# Connectors.net
KiCad netlist of a schematic drawn in Altium Designer
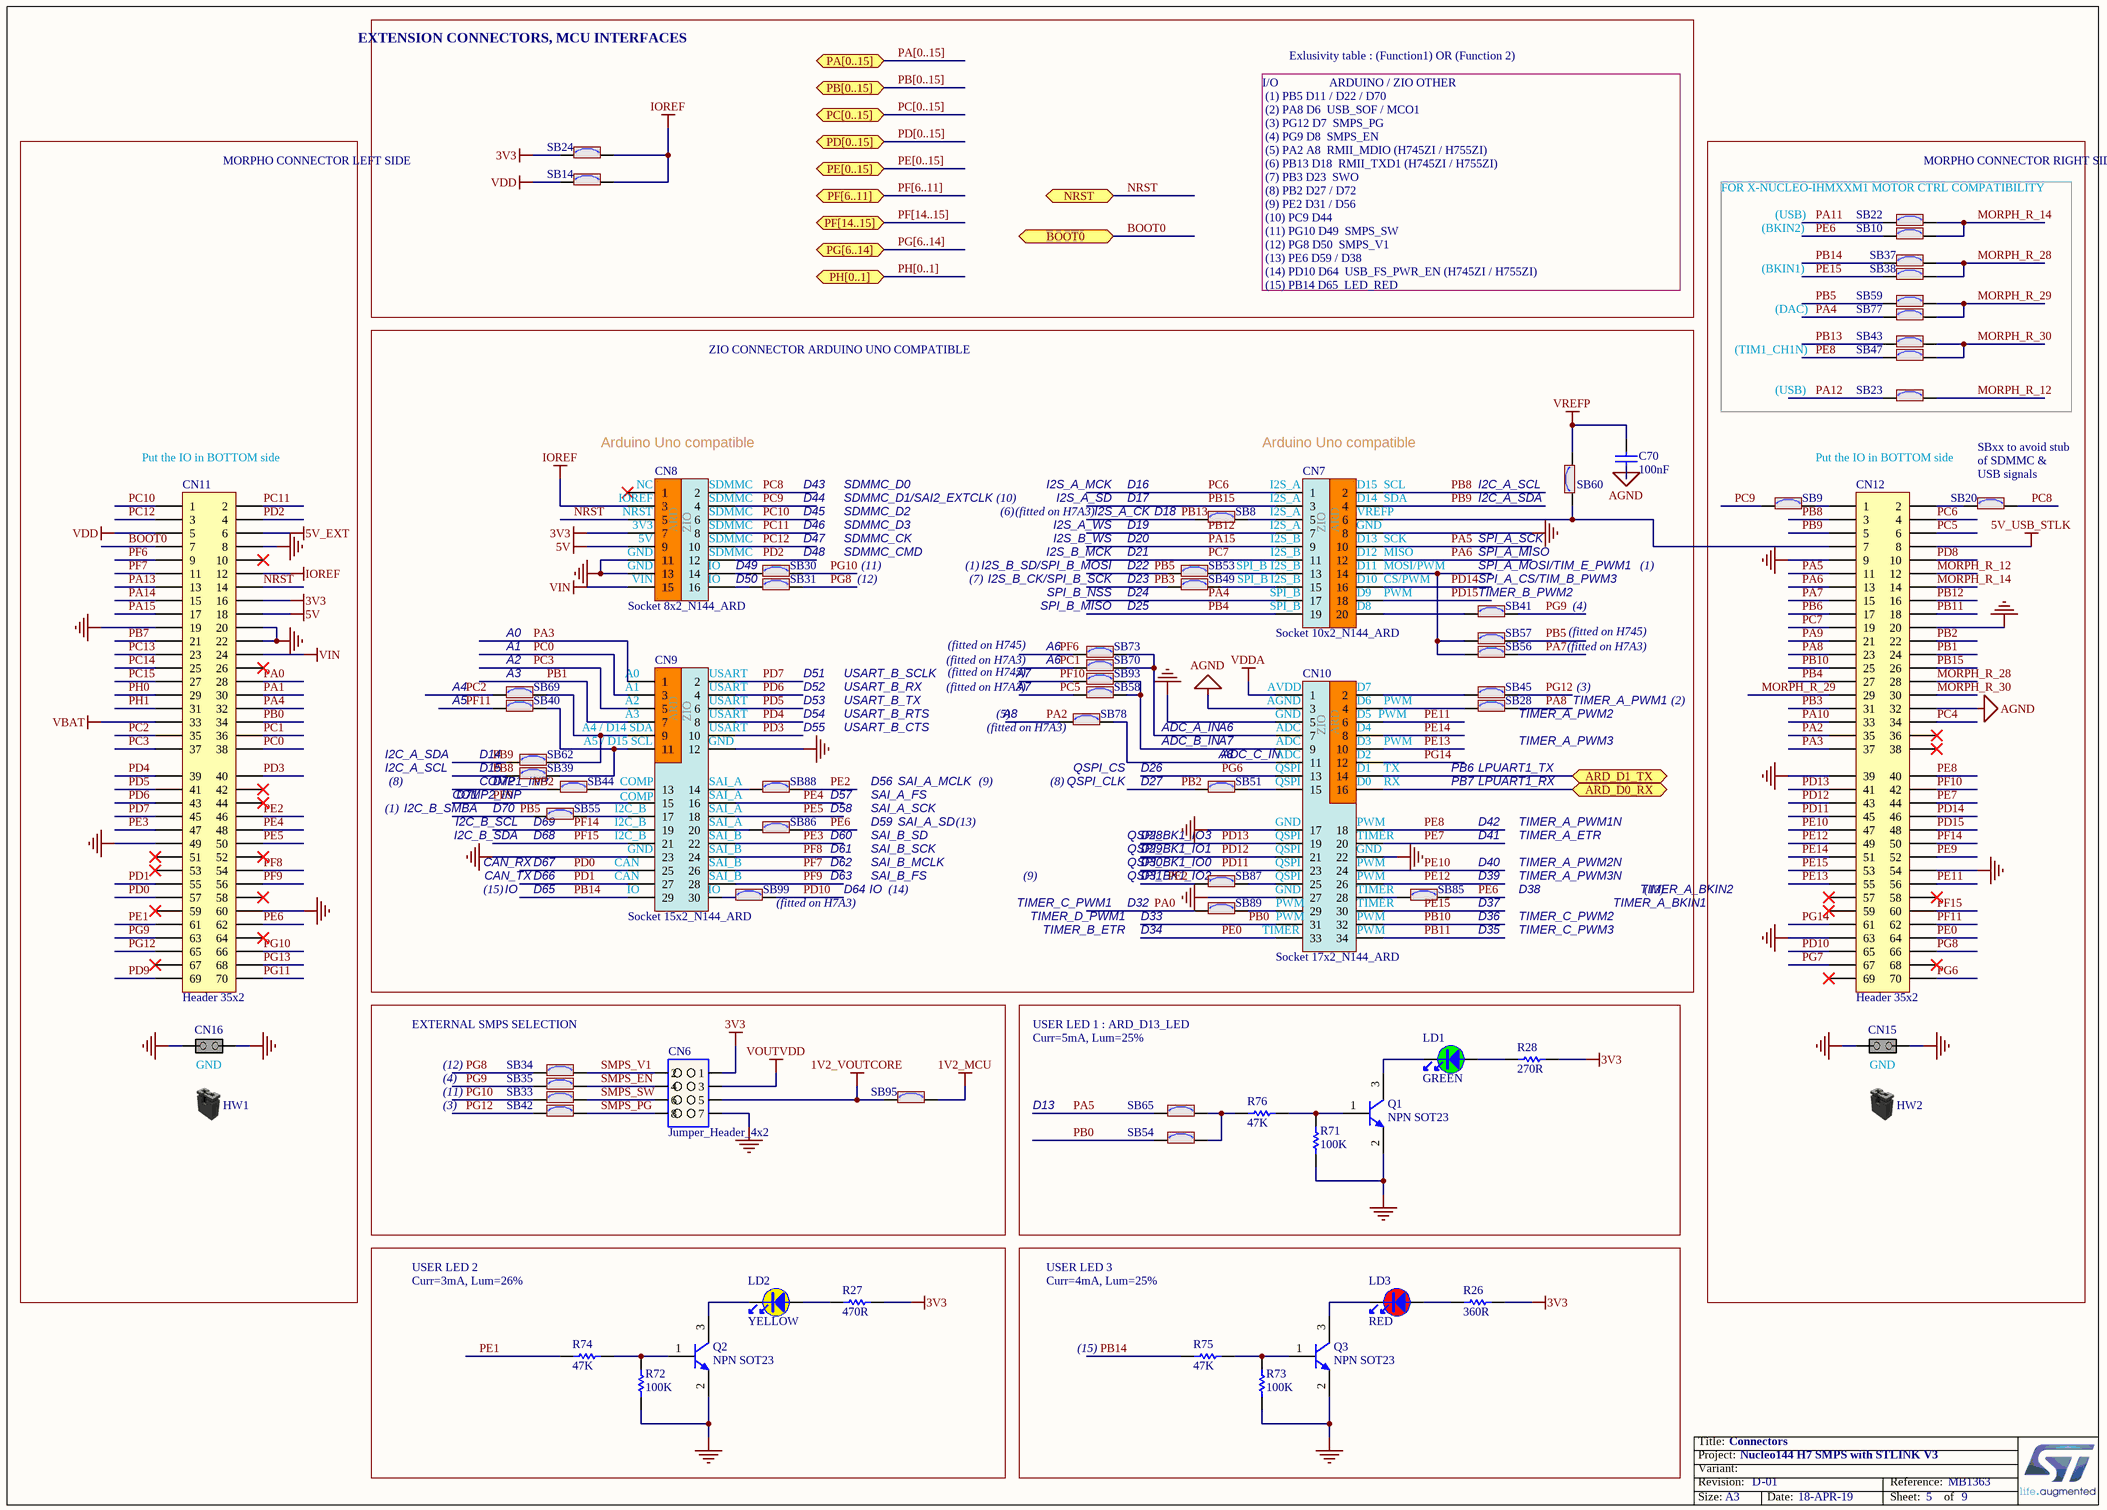
[diagram p0: Connectors.SchDoc]

(export (version "E")
  (design (tool "Eeschema 10.0.6"))
  (components
    (comp (ref "C70")
      (value "100nF")
      (footprint "C0603")
      (description "Capacitor, MLCC, 100nF, 6V3, X5R, 10%, 0603, T=0,8mm")
      (fields
        (field (name "INTERNAL_PART_NUMBER") "MCD-00237")
        (field (name "MANUFACTURER_PART_NUMBER") "CC0603KRX5R5BB104")
        (field (name "PROVIDED_BY") "SUBCO")
      )
      (libsource (lib "MCD_PARTS_database") (part "Capacitor"))
    )
    (comp (ref "CN6")
      (value "Jumper_Header_4x2")
      (footprint "CON_SAMTEC_TSW-104-07-X-D")
      (description "Header, 4x2, 2,54mm, VR, TH, Height 5.84mm/2.54mm")
      (fields
        (field (name "INTERNAL_PART_NUMBER") "MCD-00633")
        (field (name "MANUFACTURER_PART_NUMBER") "TSW-104-07-x-D")
        (field (name "PROVIDED_BY") "SUBCO")
      )
      (libsource (lib "MCD_PARTS_database") (part "Jumper_Header 4x2"))
    )
    (comp (ref "CN7")
      (value "Socket 10x2_N144_ARD")
      (footprint "CON_SAMTEC_SSW-110-23-X-D_N144_ARD")
      (description "Socket, 10x2, 2.54mm, VR, TH, Height 8.51mm/10mm, Low insertion force.")
      (fields
        (field (name "INTERNAL_PART_NUMBER") "MCD-01039")
        (field (name "MANUFACTURER_PART_NUMBER") "SSW-110-23-x-D")
        (field (name "PROVIDED_BY") "SUBCO")
      )
      (libsource (lib "MCD_PARTS_database") (part "Socket 10x2_N144_ARD"))
    )
    (comp (ref "CN8")
      (value "Socket 8x2_N144_ARD")
      (footprint "CON_SAMTEC_SSW-108-23-X-D_N144_ARD")
      (description "Socket, 8x2, 2.54mm, VR, TH, Height 8.51mm/10mm, Low insertion force.")
      (fields
        (field (name "INTERNAL_PART_NUMBER") "MCD-01037")
        (field (name "MANUFACTURER_PART_NUMBER") "SSW-108-23-x-D")
        (field (name "PROVIDED_BY") "SUBCO")
      )
      (libsource (lib "MCD_PARTS_database") (part "Socket 8x2_N144_ARD"))
    )
    (comp (ref "CN9")
      (value "Socket 15x2_N144_ARD")
      (footprint "CON_SAMTEC_SSW-115-23-X-D_N144_ARD")
      (description "Socket, 15x2, 2.54mm, VR, TH, Height 8.51mm/10mm, Low insertion force.")
      (fields
        (field (name "INTERNAL_PART_NUMBER") "MCD-01040")
        (field (name "MANUFACTURER_PART_NUMBER") "SSW-115-23-x-D")
        (field (name "PROVIDED_BY") "SUBCO")
      )
      (libsource (lib "MCD_PARTS_database") (part "Socket 15x2_N144_ARD"))
    )
    (comp (ref "CN10")
      (value "Socket 17x2_N144_ARD")
      (footprint "CON_SAMTEC_SSW-117-23-X-D_N144_ARD")
      (description "Socket, 17x2, 2.54mm, VR, TH, Height 8.51mm/10mm, Low insertion force")
      (fields
        (field (name "INTERNAL_PART_NUMBER") "MCD-01041")
        (field (name "MANUFACTURER_PART_NUMBER") "SSW-117-23-x-D")
        (field (name "PROVIDED_BY") "SUBCO")
      )
      (libsource (lib "MCD_PARTS_database") (part "Socket 17x2_N144_ARD"))
    )
    (comp (ref "CN11")
      (value "Header 35x2")
      (footprint "CON_SAMTEC_TSW-135-07-X-D")
      (description "Header, 35x2, 2,54mm, VR, TH, Height 5.84mm/2.54mm")
      (fields
        (field (name "INTERNAL_PART_NUMBER") "MCD-01210")
        (field (name "MANUFACTURER_PART_NUMBER") "TSW-135-07-x-D")
        (field (name "PROVIDED_BY") "SUBCO")
      )
      (libsource (lib "MCD_PARTS_database") (part "Header 35x2"))
    )
    (comp (ref "CN12")
      (value "Header 35x2")
      (footprint "CON_SAMTEC_TSW-135-07-X-D")
      (description "Header, 35x2, 2,54mm, VR, TH, Height 5.84mm/2.54mm")
      (fields
        (field (name "INTERNAL_PART_NUMBER") "MCD-01210")
        (field (name "MANUFACTURER_PART_NUMBER") "TSW-135-07-x-D")
        (field (name "PROVIDED_BY") "SUBCO")
      )
      (libsource (lib "MCD_PARTS_database") (part "Header 35x2"))
    )
    (comp (ref "CN15")
      (value "Jumper_Header 2x1")
      (footprint "CON_SAMTEC_TSW-102-09-X-S")
      (description "Header, 2x1, 2,54mm, VR, TH, Height 5.84mm/10.16mm")
      (fields
        (field (name "INTERNAL_PART_NUMBER") "MCD-00214")
        (field (name "MANUFACTURER_PART_NUMBER") "TSW-102-09-x-S")
        (field (name "PROVIDED_BY") "SUBCO")
      )
      (libsource (lib "MCD_PARTS_database") (part "Jumper_Header 2x1"))
    )
    (comp (ref "CN16")
      (value "Jumper_Header 2x1")
      (footprint "CON_SAMTEC_TSW-102-09-X-S")
      (description "Header, 2x1, 2,54mm, VR, TH, Height 5.84mm/10.16mm")
      (fields
        (field (name "INTERNAL_PART_NUMBER") "MCD-00214")
        (field (name "MANUFACTURER_PART_NUMBER") "TSW-102-09-x-S")
        (field (name "PROVIDED_BY") "SUBCO")
      )
      (libsource (lib "MCD_PARTS_database") (part "Jumper_Header 2x1"))
    )
    (comp (ref "HW1")
      (value "Shunt Black 2.54mm")
      (description "SHUNT 2.54mm BLACK")
      (fields
        (field (name "INTERNAL_PART_NUMBER") "MCD-00043")
        (field (name "MANUFACTURER_PART_NUMBER") "SNT-100-BK-G")
        (field (name "PROVIDED_BY") "SUBCO")
      )
      (libsource (lib "MCD_PARTS_database") (part "Shunt Black 2.54mm"))
    )
    (comp (ref "HW2")
      (value "Shunt Black 2.54mm")
      (description "SHUNT 2.54mm BLACK")
      (fields
        (field (name "INTERNAL_PART_NUMBER") "MCD-00043")
        (field (name "MANUFACTURER_PART_NUMBER") "SNT-100-BK-G")
        (field (name "PROVIDED_BY") "SUBCO")
      )
      (libsource (lib "MCD_PARTS_database") (part "Shunt Black 2.54mm"))
    )
    (comp (ref "LD1")
      (value "GREEN")
      (footprint "LED_0603_OSRAM_LG-Q396-PS-35_GREEN_1A2K_H0P4")
      (description "LED Green, 0603 SMD, Forward Voltage Typ=2V, Max=2.5V")
      (fields
        (field (name "INTERNAL_PART_NUMBER") "MCD-00588")
        (field (name "MANUFACTURER_PART_NUMBER") "LG Q396-PS-35")
        (field (name "PROVIDED_BY") "SUBCO")
      )
      (libsource (lib "MCD_PARTS_database") (part "LED_green"))
    )
    (comp (ref "LD2")
      (value "YELLOW")
      (footprint "LED_0603_OSRAM_LY-Q396-P1Q2-36_YELLOW_1A2K_H0P4")
      (description "LED Yellow, 0603 SMD, Forward Voltage min=1.7V, Typ=2V, Max=2.3V")
      (fields
        (field (name "INTERNAL_PART_NUMBER") "MCD-01061")
        (field (name "MANUFACTURER_PART_NUMBER") "LY Q396-P1Q2-36")
        (field (name "PROVIDED_BY") "SUBCO")
      )
      (libsource (lib "MCD_PARTS_database") (part "LED_yellow"))
    )
    (comp (ref "LD3")
      (value "RED")
      (footprint "LED_0603_OSRAM_LS-Q976-NR-1_RED_1A2K_H0P8")
      (description "LED Red, 0603 SMD, Forward Voltage Typ=2V, Max=2.5V")
      (fields
        (field (name "INTERNAL_PART_NUMBER") "MCD-00586")
        (field (name "MANUFACTURER_PART_NUMBER") "LS Q976-NR-1")
        (field (name "PROVIDED_BY") "SUBCO")
      )
      (libsource (lib "MCD_PARTS_database") (part "LED_red"))
    )
    (comp (ref "Q1")
      (value "NPN SOT23")
      (footprint "NPN_SOT23")
      (description "NPN Bipolar Transistor")
      (fields
        (field (name "INTERNAL_PART_NUMBER") "MCD-00073")
        (field (name "MANUFACTURER_PART_NUMBER") "BSR14")
        (field (name "PROVIDED_BY") "SUBCO")
      )
      (libsource (lib "MCD_PARTS_database") (part "9013-SOT23"))
    )
    (comp (ref "Q2")
      (value "NPN SOT23")
      (footprint "NPN_SOT23")
      (description "NPN Bipolar Transistor")
      (fields
        (field (name "INTERNAL_PART_NUMBER") "MCD-00073")
        (field (name "MANUFACTURER_PART_NUMBER") "BSR14")
        (field (name "PROVIDED_BY") "SUBCO")
      )
      (libsource (lib "MCD_PARTS_database") (part "9013-SOT23"))
    )
    (comp (ref "Q3")
      (value "NPN SOT23")
      (footprint "NPN_SOT23")
      (description "NPN Bipolar Transistor")
      (fields
        (field (name "INTERNAL_PART_NUMBER") "MCD-00073")
        (field (name "MANUFACTURER_PART_NUMBER") "BSR14")
        (field (name "PROVIDED_BY") "SUBCO")
      )
      (libsource (lib "MCD_PARTS_database") (part "9013-SOT23"))
    )
    (comp (ref "R26")
      (value "360R")
      (footprint "R0603")
      (description "Resistor,360R,0603,1%,1/10W")
      (fields
        (field (name "INTERNAL_PART_NUMBER") "MCD-00462")
        (field (name "MANUFACTURER_PART_NUMBER") "RC0603FR-07360RL")
        (field (name "PROVIDED_BY") "SUBCO")
      )
      (libsource (lib "MCD_PARTS_database") (part "Resistor"))
    )
    (comp (ref "R27")
      (value "470R")
      (footprint "R0603")
      (description "Resistor,470R,0603,1%,1/10W")
      (fields
        (field (name "INTERNAL_PART_NUMBER") "MCD-00354")
        (field (name "MANUFACTURER_PART_NUMBER") "RC0603FR-07470RL")
        (field (name "PROVIDED_BY") "SUBCO")
      )
      (libsource (lib "MCD_PARTS_database") (part "Resistor"))
    )
    (comp (ref "R28")
      (value "270R")
      (footprint "R0402")
      (description "Resistor,270R,0402,1%,1/16W")
      (fields
        (field (name "INTERNAL_PART_NUMBER") "MCD-00441")
        (field (name "MANUFACTURER_PART_NUMBER") "RC0402FR-07270RL")
        (field (name "PROVIDED_BY") "SUBCO")
      )
      (libsource (lib "MCD_PARTS_database") (part "Resistor"))
    )
    (comp (ref "R71")
      (value "100K")
      (footprint "R0603")
      (description "Resistor,100K,0603,1%,1/10W")
      (fields
        (field (name "INTERNAL_PART_NUMBER") "MCD-00223")
        (field (name "MANUFACTURER_PART_NUMBER") "RC0603FR-07100KL")
        (field (name "PROVIDED_BY") "SUBCO")
      )
      (libsource (lib "MCD_PARTS_database") (part "Resistor"))
    )
    (comp (ref "R72")
      (value "100K")
      (footprint "R0603")
      (description "Resistor,100K,0603,1%,1/10W")
      (fields
        (field (name "INTERNAL_PART_NUMBER") "MCD-00223")
        (field (name "MANUFACTURER_PART_NUMBER") "RC0603FR-07100KL")
        (field (name "PROVIDED_BY") "SUBCO")
      )
      (libsource (lib "MCD_PARTS_database") (part "Resistor"))
    )
    (comp (ref "R73")
      (value "100K")
      (footprint "R0603")
      (description "Resistor,100K,0603,1%,1/10W")
      (fields
        (field (name "INTERNAL_PART_NUMBER") "MCD-00223")
        (field (name "MANUFACTURER_PART_NUMBER") "RC0603FR-07100KL")
        (field (name "PROVIDED_BY") "SUBCO")
      )
      (libsource (lib "MCD_PARTS_database") (part "Resistor"))
    )
    (comp (ref "R74")
      (value "47K")
      (footprint "R0603")
      (description "Resistor,47K,0603,1%,1/10W")
      (fields
        (field (name "INTERNAL_PART_NUMBER") "MCD-00222")
        (field (name "MANUFACTURER_PART_NUMBER") "RC0603FR-0747KL")
        (field (name "PROVIDED_BY") "SUBCO")
      )
      (libsource (lib "MCD_PARTS_database") (part "Resistor"))
    )
    (comp (ref "R75")
      (value "47K")
      (footprint "R0603")
      (description "Resistor,47K,0603,1%,1/10W")
      (fields
        (field (name "INTERNAL_PART_NUMBER") "MCD-00222")
        (field (name "MANUFACTURER_PART_NUMBER") "RC0603FR-0747KL")
        (field (name "PROVIDED_BY") "SUBCO")
      )
      (libsource (lib "MCD_PARTS_database") (part "Resistor"))
    )
    (comp (ref "R76")
      (value "47K")
      (footprint "R0603")
      (description "Resistor,47K,0603,1%,1/10W")
      (fields
        (field (name "INTERNAL_PART_NUMBER") "MCD-00222")
        (field (name "MANUFACTURER_PART_NUMBER") "RC0603FR-0747KL")
        (field (name "PROVIDED_BY") "SUBCO")
      )
      (libsource (lib "MCD_PARTS_database") (part "Resistor"))
    )
    (comp (ref "SB8")
      (value "SB_ON")
      (footprint "SOLDER-BRIDGE_R0603-0R")
      (description "Solder Bridge ON")
      (fields
        (field (name "INTERNAL_PART_NUMBER") "MCD-00071")
        (field (name "MANUFACTURER_PART_NUMBER") "RC0603JR-070RL")
        (field (name "PROVIDED_BY") "SUBCO")
      )
      (libsource (lib "MCD_PARTS_database") (part "SB_ON"))
    )
    (comp (ref "SB9")
      (value "SB_ON")
      (footprint "SOLDER-BRIDGE_R0603-0R")
      (description "Solder Bridge ON")
      (fields
        (field (name "INTERNAL_PART_NUMBER") "MCD-00071")
        (field (name "MANUFACTURER_PART_NUMBER") "RC0603JR-070RL")
        (field (name "PROVIDED_BY") "SUBCO")
      )
      (libsource (lib "MCD_PARTS_database") (part "SB_ON"))
    )
    (comp (ref "SB10")
      (value "SB_ON")
      (footprint "SOLDER-BRIDGE_R0603-0R")
      (description "Solder Bridge ON")
      (fields
        (field (name "INTERNAL_PART_NUMBER") "MCD-00071")
        (field (name "MANUFACTURER_PART_NUMBER") "RC0603JR-070RL")
        (field (name "PROVIDED_BY") "SUBCO")
      )
      (libsource (lib "MCD_PARTS_database") (part "SB_ON"))
    )
    (comp (ref "SB14")
      (value "SB_ON")
      (footprint "SOLDER-BRIDGE_R0402-0R")
      (description "Solder Bridge 0402 ON")
      (fields
        (field (name "INTERNAL_PART_NUMBER") "MCD-01618")
        (field (name "MANUFACTURER_PART_NUMBER") "RC0402JR-070RL")
        (field (name "PROVIDED_BY") "SUBCO")
      )
      (libsource (lib "MCD_PARTS_database") (part "SB_ON"))
    )
    (comp (ref "SB20")
      (value "SB_ON")
      (footprint "SOLDER-BRIDGE_R0603-0R")
      (description "Solder Bridge ON")
      (fields
        (field (name "INTERNAL_PART_NUMBER") "MCD-00071")
        (field (name "MANUFACTURER_PART_NUMBER") "RC0603JR-070RL")
        (field (name "PROVIDED_BY") "SUBCO")
      )
      (libsource (lib "MCD_PARTS_database") (part "SB_ON"))
    )
    (comp (ref "SB22")
      (value "SB_ON")
      (footprint "SOLDER-BRIDGE_R0603-0R")
      (description "Solder Bridge ON")
      (fields
        (field (name "INTERNAL_PART_NUMBER") "MCD-00071")
        (field (name "MANUFACTURER_PART_NUMBER") "RC0603JR-070RL")
        (field (name "PROVIDED_BY") "SUBCO")
      )
      (libsource (lib "MCD_PARTS_database") (part "SB_ON"))
    )
    (comp (ref "SB23")
      (value "SB_ON")
      (footprint "SOLDER-BRIDGE_R0603-0R")
      (description "Solder Bridge ON")
      (fields
        (field (name "INTERNAL_PART_NUMBER") "MCD-00071")
        (field (name "MANUFACTURER_PART_NUMBER") "RC0603JR-070RL")
        (field (name "PROVIDED_BY") "SUBCO")
      )
      (libsource (lib "MCD_PARTS_database") (part "SB_ON"))
    )
    (comp (ref "SB24")
      (value "SB_ON")
      (footprint "SOLDER-BRIDGE_R0402-0R")
      (description "Solder Bridge 0402 ON")
      (fields
        (field (name "INTERNAL_PART_NUMBER") "MCD-01618")
        (field (name "MANUFACTURER_PART_NUMBER") "RC0402JR-070RL")
        (field (name "PROVIDED_BY") "SUBCO")
      )
      (libsource (lib "MCD_PARTS_database") (part "SB_ON"))
    )
    (comp (ref "SB28")
      (value "SB_ON")
      (footprint "SOLDER-BRIDGE_R0603-0R")
      (description "Solder Bridge ON")
      (fields
        (field (name "INTERNAL_PART_NUMBER") "MCD-00071")
        (field (name "MANUFACTURER_PART_NUMBER") "RC0603JR-070RL")
        (field (name "PROVIDED_BY") "SUBCO")
      )
      (libsource (lib "MCD_PARTS_database") (part "SB_ON"))
    )
    (comp (ref "SB30")
      (value "SB_ON")
      (footprint "SOLDER-BRIDGE_R0603-0R")
      (description "Solder Bridge ON")
      (fields
        (field (name "INTERNAL_PART_NUMBER") "MCD-00071")
        (field (name "MANUFACTURER_PART_NUMBER") "RC0603JR-070RL")
        (field (name "PROVIDED_BY") "SUBCO")
      )
      (libsource (lib "MCD_PARTS_database") (part "SB_ON"))
    )
    (comp (ref "SB31")
      (value "SB_ON")
      (footprint "SOLDER-BRIDGE_R0603-0R")
      (description "Solder Bridge ON")
      (fields
        (field (name "INTERNAL_PART_NUMBER") "MCD-00071")
        (field (name "MANUFACTURER_PART_NUMBER") "RC0603JR-070RL")
        (field (name "PROVIDED_BY") "SUBCO")
      )
      (libsource (lib "MCD_PARTS_database") (part "SB_ON"))
    )
    (comp (ref "SB33")
      (value "SB_ON")
      (footprint "SOLDER-BRIDGE_R0603-0R")
      (description "Solder Bridge ON")
      (fields
        (field (name "INTERNAL_PART_NUMBER") "MCD-00071")
        (field (name "MANUFACTURER_PART_NUMBER") "RC0603JR-070RL")
        (field (name "PROVIDED_BY") "SUBCO")
      )
      (libsource (lib "") (part "SB_ON_2"))
    )
    (comp (ref "SB34")
      (value "SB_ON")
      (footprint "SOLDER-BRIDGE_R0603-0R")
      (description "Solder Bridge ON")
      (fields
        (field (name "INTERNAL_PART_NUMBER") "MCD-00071")
        (field (name "MANUFACTURER_PART_NUMBER") "RC0603JR-070RL")
        (field (name "PROVIDED_BY") "SUBCO")
      )
      (libsource (lib "") (part "SB_ON_2"))
    )
    (comp (ref "SB35")
      (value "SB_ON")
      (footprint "SOLDER-BRIDGE_R0603-0R")
      (description "Solder Bridge ON")
      (fields
        (field (name "INTERNAL_PART_NUMBER") "MCD-00071")
        (field (name "MANUFACTURER_PART_NUMBER") "RC0603JR-070RL")
        (field (name "PROVIDED_BY") "SUBCO")
      )
      (libsource (lib "") (part "SB_ON_2"))
    )
    (comp (ref "SB37")
      (value "SB_ON")
      (footprint "SOLDER-BRIDGE_R0402-0R")
      (description "Solder Bridge 0402 ON")
      (fields
        (field (name "INTERNAL_PART_NUMBER") "MCD-01618")
        (field (name "MANUFACTURER_PART_NUMBER") "RC0402JR-070RL")
        (field (name "PROVIDED_BY") "SUBCO")
      )
      (libsource (lib "MCD_PARTS_database") (part "SB_ON"))
    )
    (comp (ref "SB38")
      (value "SB_ON")
      (footprint "SOLDER-BRIDGE_R0402-0R")
      (description "Solder Bridge 0402 ON")
      (fields
        (field (name "INTERNAL_PART_NUMBER") "MCD-01618")
        (field (name "MANUFACTURER_PART_NUMBER") "RC0402JR-070RL")
        (field (name "PROVIDED_BY") "SUBCO")
      )
      (libsource (lib "MCD_PARTS_database") (part "SB_ON"))
    )
    (comp (ref "SB39")
      (value "SB_ON")
      (footprint "SOLDER-BRIDGE_R0603-0R")
      (description "Solder Bridge ON")
      (fields
        (field (name "INTERNAL_PART_NUMBER") "MCD-00071")
        (field (name "MANUFACTURER_PART_NUMBER") "RC0603JR-070RL")
        (field (name "PROVIDED_BY") "SUBCO")
      )
      (libsource (lib "MCD_PARTS_database") (part "SB_ON"))
    )
    (comp (ref "SB40")
      (value "SB_ON")
      (footprint "SOLDER-BRIDGE_R0603-0R")
      (description "Solder Bridge ON")
      (fields
        (field (name "INTERNAL_PART_NUMBER") "MCD-00071")
        (field (name "MANUFACTURER_PART_NUMBER") "RC0603JR-070RL")
        (field (name "PROVIDED_BY") "SUBCO")
      )
      (libsource (lib "MCD_PARTS_database") (part "SB_ON"))
    )
    (comp (ref "SB41")
      (value "SB_ON")
      (footprint "SOLDER-BRIDGE_R0603-0R")
      (description "Solder Bridge ON")
      (fields
        (field (name "INTERNAL_PART_NUMBER") "MCD-00071")
        (field (name "MANUFACTURER_PART_NUMBER") "RC0603JR-070RL")
        (field (name "PROVIDED_BY") "SUBCO")
      )
      (libsource (lib "MCD_PARTS_database") (part "SB_ON"))
    )
    (comp (ref "SB42")
      (value "SB_ON")
      (footprint "SOLDER-BRIDGE_R0603-0R")
      (description "Solder Bridge ON")
      (fields
        (field (name "INTERNAL_PART_NUMBER") "MCD-00071")
        (field (name "MANUFACTURER_PART_NUMBER") "RC0603JR-070RL")
        (field (name "PROVIDED_BY") "SUBCO")
      )
      (libsource (lib "") (part "SB_ON_2"))
    )
    (comp (ref "SB43")
      (value "SB_ON")
      (footprint "SOLDER-BRIDGE_R0603-0R")
      (description "Solder Bridge ON")
      (fields
        (field (name "INTERNAL_PART_NUMBER") "MCD-00071")
        (field (name "MANUFACTURER_PART_NUMBER") "RC0603JR-070RL")
        (field (name "PROVIDED_BY") "SUBCO")
      )
      (libsource (lib "MCD_PARTS_database") (part "SB_ON"))
    )
    (comp (ref "SB44")
      (value "SB_ON")
      (footprint "SOLDER-BRIDGE_R0603-0R")
      (description "Solder Bridge ON")
      (fields
        (field (name "INTERNAL_PART_NUMBER") "MCD-00071")
        (field (name "MANUFACTURER_PART_NUMBER") "RC0603JR-070RL")
        (field (name "PROVIDED_BY") "SUBCO")
      )
      (libsource (lib "MCD_PARTS_database") (part "SB_ON"))
    )
    (comp (ref "SB45")
      (value "SB_ON")
      (footprint "SOLDER-BRIDGE_R0603-0R")
      (description "Solder Bridge ON")
      (fields
        (field (name "INTERNAL_PART_NUMBER") "MCD-00071")
        (field (name "MANUFACTURER_PART_NUMBER") "RC0603JR-070RL")
        (field (name "PROVIDED_BY") "SUBCO")
      )
      (libsource (lib "MCD_PARTS_database") (part "SB_ON"))
    )
    (comp (ref "SB47")
      (value "SB_ON")
      (footprint "SOLDER-BRIDGE_R0603-0R")
      (description "Solder Bridge ON")
      (fields
        (field (name "INTERNAL_PART_NUMBER") "MCD-00071")
        (field (name "MANUFACTURER_PART_NUMBER") "RC0603JR-070RL")
        (field (name "PROVIDED_BY") "SUBCO")
      )
      (libsource (lib "MCD_PARTS_database") (part "SB_ON"))
    )
    (comp (ref "SB49")
      (value "SB_ON")
      (footprint "SOLDER-BRIDGE_R0603-0R")
      (description "Solder Bridge ON")
      (fields
        (field (name "INTERNAL_PART_NUMBER") "MCD-00071")
        (field (name "MANUFACTURER_PART_NUMBER") "RC0603JR-070RL")
        (field (name "PROVIDED_BY") "SUBCO")
      )
      (libsource (lib "MCD_PARTS_database") (part "SB_ON"))
    )
    (comp (ref "SB51")
      (value "SB_ON")
      (footprint "SOLDER-BRIDGE_R0603-0R")
      (description "Solder Bridge ON")
      (fields
        (field (name "INTERNAL_PART_NUMBER") "MCD-00071")
        (field (name "MANUFACTURER_PART_NUMBER") "RC0603JR-070RL")
        (field (name "PROVIDED_BY") "SUBCO")
      )
      (libsource (lib "MCD_PARTS_database") (part "SB_ON"))
    )
    (comp (ref "SB53")
      (value "SB_ON")
      (footprint "SOLDER-BRIDGE_R0603-0R")
      (description "Solder Bridge ON")
      (fields
        (field (name "INTERNAL_PART_NUMBER") "MCD-00071")
        (field (name "MANUFACTURER_PART_NUMBER") "RC0603JR-070RL")
        (field (name "PROVIDED_BY") "SUBCO")
      )
      (libsource (lib "MCD_PARTS_database") (part "SB_ON"))
    )
    (comp (ref "SB54")
      (value "SB_ON")
      (footprint "SOLDER-BRIDGE_R0603-0R")
      (description "Solder Bridge ON")
      (fields
        (field (name "INTERNAL_PART_NUMBER") "MCD-00071")
        (field (name "MANUFACTURER_PART_NUMBER") "RC0603JR-070RL")
        (field (name "PROVIDED_BY") "SUBCO")
      )
      (libsource (lib "MCD_PARTS_database") (part "SB_ON"))
    )
    (comp (ref "SB55")
      (value "SB_ON")
      (footprint "SOLDER-BRIDGE_R0603-0R")
      (description "Solder Bridge ON")
      (fields
        (field (name "INTERNAL_PART_NUMBER") "MCD-00071")
        (field (name "MANUFACTURER_PART_NUMBER") "RC0603JR-070RL")
        (field (name "PROVIDED_BY") "SUBCO")
      )
      (libsource (lib "MCD_PARTS_database") (part "SB_ON"))
    )
    (comp (ref "SB56")
      (value "SB_ON")
      (footprint "SOLDER-BRIDGE_R0603-0R")
      (description "Solder Bridge ON")
      (fields
        (field (name "INTERNAL_PART_NUMBER") "MCD-00071")
        (field (name "MANUFACTURER_PART_NUMBER") "RC0603JR-070RL")
        (field (name "PROVIDED_BY") "SUBCO")
      )
      (libsource (lib "MCD_PARTS_database") (part "SB_ON"))
    )
    (comp (ref "SB57")
      (value "SB_ON")
      (footprint "SOLDER-BRIDGE_R0603-0R")
      (description "Solder Bridge ON")
      (fields
        (field (name "INTERNAL_PART_NUMBER") "MCD-00071")
        (field (name "MANUFACTURER_PART_NUMBER") "RC0603JR-070RL")
        (field (name "PROVIDED_BY") "SUBCO")
      )
      (libsource (lib "MCD_PARTS_database") (part "SB_ON"))
    )
    (comp (ref "SB58")
      (value "SB_ON")
      (footprint "SOLDER-BRIDGE_R0603-0R")
      (description "Solder Bridge ON")
      (fields
        (field (name "INTERNAL_PART_NUMBER") "MCD-00071")
        (field (name "MANUFACTURER_PART_NUMBER") "RC0603JR-070RL")
        (field (name "PROVIDED_BY") "SUBCO")
      )
      (libsource (lib "MCD_PARTS_database") (part "SB_ON"))
    )
    (comp (ref "SB59")
      (value "SB_ON")
      (footprint "SOLDER-BRIDGE_R0603-0R")
      (description "Solder Bridge ON")
      (fields
        (field (name "INTERNAL_PART_NUMBER") "MCD-00071")
        (field (name "MANUFACTURER_PART_NUMBER") "RC0603JR-070RL")
        (field (name "PROVIDED_BY") "SUBCO")
      )
      (libsource (lib "MCD_PARTS_database") (part "SB_ON"))
    )
    (comp (ref "SB60")
      (value "SB_ON")
      (footprint "SOLDER-BRIDGE_R0603-0R")
      (description "Solder Bridge ON")
      (fields
        (field (name "INTERNAL_PART_NUMBER") "MCD-00071")
        (field (name "MANUFACTURER_PART_NUMBER") "RC0603JR-070RL")
        (field (name "PROVIDED_BY") "SUBCO")
      )
      (libsource (lib "") (part "SB_ON_1"))
    )
    (comp (ref "SB62")
      (value "SB_ON")
      (footprint "SOLDER-BRIDGE_R0603-0R")
      (description "Solder Bridge ON")
      (fields
        (field (name "INTERNAL_PART_NUMBER") "MCD-00071")
        (field (name "MANUFACTURER_PART_NUMBER") "RC0603JR-070RL")
        (field (name "PROVIDED_BY") "SUBCO")
      )
      (libsource (lib "MCD_PARTS_database") (part "SB_ON"))
    )
    (comp (ref "SB65")
      (value "SB_ON")
      (footprint "SOLDER-BRIDGE_R0603-0R")
      (description "Solder Bridge ON")
      (fields
        (field (name "INTERNAL_PART_NUMBER") "MCD-00071")
        (field (name "MANUFACTURER_PART_NUMBER") "RC0603JR-070RL")
        (field (name "PROVIDED_BY") "SUBCO")
      )
      (libsource (lib "MCD_PARTS_database") (part "SB_ON"))
    )
    (comp (ref "SB69")
      (value "SB_ON")
      (footprint "SOLDER-BRIDGE_R0603-0R")
      (description "Solder Bridge ON")
      (fields
        (field (name "INTERNAL_PART_NUMBER") "MCD-00071")
        (field (name "MANUFACTURER_PART_NUMBER") "RC0603JR-070RL")
        (field (name "PROVIDED_BY") "SUBCO")
      )
      (libsource (lib "MCD_PARTS_database") (part "SB_ON"))
    )
    (comp (ref "SB70")
      (value "SB_ON")
      (footprint "SOLDER-BRIDGE_R0603-0R")
      (description "Solder Bridge ON")
      (fields
        (field (name "INTERNAL_PART_NUMBER") "MCD-00071")
        (field (name "MANUFACTURER_PART_NUMBER") "RC0603JR-070RL")
        (field (name "PROVIDED_BY") "SUBCO")
      )
      (libsource (lib "MCD_PARTS_database") (part "SB_ON"))
    )
    (comp (ref "SB73")
      (value "SB_ON")
      (footprint "SOLDER-BRIDGE_R0603-0R")
      (description "Solder Bridge ON")
      (fields
        (field (name "INTERNAL_PART_NUMBER") "MCD-00071")
        (field (name "MANUFACTURER_PART_NUMBER") "RC0603JR-070RL")
        (field (name "PROVIDED_BY") "SUBCO")
      )
      (libsource (lib "MCD_PARTS_database") (part "SB_ON"))
    )
    (comp (ref "SB77")
      (value "SB_ON")
      (footprint "SOLDER-BRIDGE_R0603-0R")
      (description "Solder Bridge ON")
      (fields
        (field (name "INTERNAL_PART_NUMBER") "MCD-00071")
        (field (name "MANUFACTURER_PART_NUMBER") "RC0603JR-070RL")
        (field (name "PROVIDED_BY") "SUBCO")
      )
      (libsource (lib "MCD_PARTS_database") (part "SB_ON"))
    )
    (comp (ref "SB78")
      (value "SB_ON")
      (footprint "SOLDER-BRIDGE_R0603-0R")
      (description "Solder Bridge ON")
      (fields
        (field (name "INTERNAL_PART_NUMBER") "MCD-00071")
        (field (name "MANUFACTURER_PART_NUMBER") "RC0603JR-070RL")
        (field (name "PROVIDED_BY") "SUBCO")
      )
      (libsource (lib "MCD_PARTS_database") (part "SB_ON"))
    )
    (comp (ref "SB85")
      (value "SB_ON")
      (footprint "SOLDER-BRIDGE_R0603-0R")
      (description "Solder Bridge ON")
      (fields
        (field (name "INTERNAL_PART_NUMBER") "MCD-00071")
        (field (name "MANUFACTURER_PART_NUMBER") "RC0603JR-070RL")
        (field (name "PROVIDED_BY") "SUBCO")
      )
      (libsource (lib "MCD_PARTS_database") (part "SB_ON"))
    )
    (comp (ref "SB86")
      (value "SB_ON")
      (footprint "SOLDER-BRIDGE_R0603-0R")
      (description "Solder Bridge ON")
      (fields
        (field (name "INTERNAL_PART_NUMBER") "MCD-00071")
        (field (name "MANUFACTURER_PART_NUMBER") "RC0603JR-070RL")
        (field (name "PROVIDED_BY") "SUBCO")
      )
      (libsource (lib "MCD_PARTS_database") (part "SB_ON"))
    )
    (comp (ref "SB87")
      (value "SB_ON")
      (footprint "SOLDER-BRIDGE_R0603-0R")
      (description "Solder Bridge ON")
      (fields
        (field (name "INTERNAL_PART_NUMBER") "MCD-00071")
        (field (name "MANUFACTURER_PART_NUMBER") "RC0603JR-070RL")
        (field (name "PROVIDED_BY") "SUBCO")
      )
      (libsource (lib "MCD_PARTS_database") (part "SB_ON"))
    )
    (comp (ref "SB88")
      (value "SB_ON")
      (footprint "SOLDER-BRIDGE_R0603-0R")
      (description "Solder Bridge ON")
      (fields
        (field (name "INTERNAL_PART_NUMBER") "MCD-00071")
        (field (name "MANUFACTURER_PART_NUMBER") "RC0603JR-070RL")
        (field (name "PROVIDED_BY") "SUBCO")
      )
      (libsource (lib "MCD_PARTS_database") (part "SB_ON"))
    )
    (comp (ref "SB89")
      (value "SB_ON")
      (footprint "SOLDER-BRIDGE_R0603-0R")
      (description "Solder Bridge ON")
      (fields
        (field (name "INTERNAL_PART_NUMBER") "MCD-00071")
        (field (name "MANUFACTURER_PART_NUMBER") "RC0603JR-070RL")
        (field (name "PROVIDED_BY") "SUBCO")
      )
      (libsource (lib "MCD_PARTS_database") (part "SB_ON"))
    )
    (comp (ref "SB93")
      (value "SB_ON")
      (footprint "SOLDER-BRIDGE_R0603-0R")
      (description "Solder Bridge ON")
      (fields
        (field (name "INTERNAL_PART_NUMBER") "MCD-00071")
        (field (name "MANUFACTURER_PART_NUMBER") "RC0603JR-070RL")
        (field (name "PROVIDED_BY") "SUBCO")
      )
      (libsource (lib "MCD_PARTS_database") (part "SB_ON"))
    )
    (comp (ref "SB95")
      (value "SB_ON")
      (footprint "SOLDER-BRIDGE_R0603-0R")
      (description "Solder Bridge ON")
      (fields
        (field (name "INTERNAL_PART_NUMBER") "MCD-00071")
        (field (name "MANUFACTURER_PART_NUMBER") "RC0603JR-070RL")
        (field (name "PROVIDED_BY") "SUBCO")
      )
      (libsource (lib "MCD_PARTS_database") (part "SB_ON"))
    )
    (comp (ref "SB99")
      (value "SB_ON")
      (footprint "SOLDER-BRIDGE_R0603-0R")
      (description "Solder Bridge ON")
      (fields
        (field (name "INTERNAL_PART_NUMBER") "MCD-00071")
        (field (name "MANUFACTURER_PART_NUMBER") "RC0603JR-070RL")
        (field (name "PROVIDED_BY") "SUBCO")
      )
      (libsource (lib "MCD_PARTS_database") (part "SB_ON"))
    )
  )
  (nets
    (net (code "1") (name "/ARD_D0_RX") (class "Default")
      (node (ref "CN10") (pin "16") (pinfunction "16_16") (pintype "passive"))
    )
    (net (code "2") (name "/ARD_D1_TX") (class "Default")
      (node (ref "CN10") (pin "14") (pinfunction "14_14") (pintype "passive"))
    )
    (net (code "3") (name "/BOOT0") (class "Default")
      (node (ref "CN11") (pin "7") (pinfunction "7_7") (pintype "passive"))
    )
    (net (code "4") (name "/MORPH_R_12") (class "Default")
      (node (ref "CN12") (pin "12") (pinfunction "12_12") (pintype "passive"))
      (node (ref "SB23") (pin "2") (pinfunction "2_2") (pintype "passive"))
    )
    (net (code "5") (name "/MORPH_R_14") (class "Default")
      (node (ref "CN12") (pin "14") (pinfunction "14_14") (pintype "passive"))
      (node (ref "SB10") (pin "2") (pinfunction "2_2") (pintype "passive"))
      (node (ref "SB22") (pin "2") (pinfunction "2_2") (pintype "passive"))
    )
    (net (code "6") (name "/MORPH_R_28") (class "Default")
      (node (ref "CN12") (pin "28") (pinfunction "28_28") (pintype "passive"))
      (node (ref "SB37") (pin "2") (pinfunction "2_2") (pintype "passive"))
      (node (ref "SB38") (pin "2") (pinfunction "2_2") (pintype "passive"))
    )
    (net (code "7") (name "/MORPH_R_29") (class "Default")
      (node (ref "CN12") (pin "29") (pinfunction "29_29") (pintype "passive"))
      (node (ref "SB59") (pin "2") (pinfunction "2_2") (pintype "passive"))
      (node (ref "SB77") (pin "2") (pinfunction "2_2") (pintype "passive"))
    )
    (net (code "8") (name "/MORPH_R_30") (class "Default")
      (node (ref "CN12") (pin "30") (pinfunction "30_30") (pintype "passive"))
      (node (ref "SB43") (pin "2") (pinfunction "2_2") (pintype "passive"))
      (node (ref "SB47") (pin "2") (pinfunction "2_2") (pintype "passive"))
    )
    (net (code "9") (name "/NRST") (class "Default")
      (node (ref "CN11") (pin "14") (pinfunction "14_14") (pintype "passive"))
      (node (ref "CN8") (pin "5") (pinfunction "5_5") (pintype "passive"))
    )
    (net (code "10") (name "/PA0") (class "Default")
      (node (ref "CN11") (pin "28") (pinfunction "28_28") (pintype "passive"))
      (node (ref "SB89") (pin "1") (pinfunction "1_1") (pintype "passive"))
    )
    (net (code "11") (name "/PA1") (class "Default")
      (node (ref "CN11") (pin "30") (pinfunction "30_30") (pintype "passive"))
    )
    (net (code "12") (name "/PA2") (class "Default")
      (node (ref "CN12") (pin "35") (pinfunction "35_35") (pintype "passive"))
      (node (ref "SB78") (pin "1") (pinfunction "1_1") (pintype "passive"))
    )
    (net (code "13") (name "/PA3") (class "Default")
      (node (ref "CN12") (pin "37") (pinfunction "37_37") (pintype "passive"))
      (node (ref "CN9") (pin "1") (pinfunction "1_1") (pintype "passive"))
    )
    (net (code "14") (name "/PA4") (class "Default")
      (node (ref "CN11") (pin "32") (pinfunction "32_32") (pintype "passive"))
      (node (ref "CN7") (pin "17") (pinfunction "17_17") (pintype "passive"))
      (node (ref "SB77") (pin "1") (pinfunction "1_1") (pintype "passive"))
    )
    (net (code "15") (name "/PA5") (class "Default")
      (node (ref "CN12") (pin "11") (pinfunction "11_11") (pintype "passive"))
      (node (ref "CN7") (pin "10") (pinfunction "10_10") (pintype "passive"))
      (node (ref "SB65") (pin "1") (pinfunction "1_1") (pintype "passive"))
    )
    (net (code "16") (name "/PA6") (class "Default")
      (node (ref "CN12") (pin "13") (pinfunction "13_13") (pintype "passive"))
      (node (ref "CN7") (pin "12") (pinfunction "12_12") (pintype "passive"))
    )
    (net (code "17") (name "/PA7") (class "Default")
      (node (ref "CN12") (pin "15") (pinfunction "15_15") (pintype "passive"))
      (node (ref "SB56") (pin "2") (pinfunction "2_2") (pintype "passive"))
    )
    (net (code "18") (name "/PA8") (class "Default")
      (node (ref "CN12") (pin "23") (pinfunction "23_23") (pintype "passive"))
      (node (ref "SB28") (pin "2") (pinfunction "2_2") (pintype "passive"))
    )
    (net (code "19") (name "/PA9") (class "Default")
      (node (ref "CN12") (pin "21") (pinfunction "21_21") (pintype "passive"))
    )
    (net (code "20") (name "/PA10") (class "Default")
      (node (ref "CN12") (pin "33") (pinfunction "33_33") (pintype "passive"))
    )
    (net (code "21") (name "/PA11") (class "Default")
      (node (ref "SB22") (pin "1") (pinfunction "1_1") (pintype "passive"))
    )
    (net (code "22") (name "/PA12") (class "Default")
      (node (ref "SB23") (pin "1") (pinfunction "1_1") (pintype "passive"))
    )
    (net (code "23") (name "/PA13") (class "Default")
      (node (ref "CN11") (pin "13") (pinfunction "13_13") (pintype "passive"))
    )
    (net (code "24") (name "/PA14") (class "Default")
      (node (ref "CN11") (pin "15") (pinfunction "15_15") (pintype "passive"))
    )
    (net (code "25") (name "/PA15") (class "Default")
      (node (ref "CN11") (pin "17") (pinfunction "17_17") (pintype "passive"))
      (node (ref "CN7") (pin "9") (pinfunction "9_9") (pintype "passive"))
    )
    (net (code "27") (name "/PB0") (class "Default")
      (node (ref "CN10") (pin "31") (pinfunction "31_31") (pintype "passive"))
      (node (ref "CN11") (pin "34") (pinfunction "34_34") (pintype "passive"))
      (node (ref "SB54") (pin "1") (pinfunction "1_1") (pintype "passive"))
    )
    (net (code "28") (name "/PB1") (class "Default")
      (node (ref "CN12") (pin "24") (pinfunction "24_24") (pintype "passive"))
      (node (ref "CN9") (pin "7") (pinfunction "7_7") (pintype "passive"))
    )
    (net (code "29") (name "/PB2") (class "Default")
      (node (ref "CN12") (pin "22") (pinfunction "22_22") (pintype "passive"))
      (node (ref "SB44") (pin "1") (pinfunction "1_1") (pintype "passive"))
      (node (ref "SB51") (pin "1") (pinfunction "1_1") (pintype "passive"))
    )
    (net (code "30") (name "/PB3") (class "Default")
      (node (ref "CN12") (pin "31") (pinfunction "31_31") (pintype "passive"))
      (node (ref "SB49") (pin "1") (pinfunction "1_1") (pintype "passive"))
    )
    (net (code "31") (name "/PB4") (class "Default")
      (node (ref "CN12") (pin "27") (pinfunction "27_27") (pintype "passive"))
      (node (ref "CN7") (pin "19") (pinfunction "19_19") (pintype "passive"))
    )
    (net (code "32") (name "/PB5") (class "Default")
      (node (ref "SB53") (pin "1") (pinfunction "1_1") (pintype "passive"))
      (node (ref "SB55") (pin "1") (pinfunction "1_1") (pintype "passive"))
      (node (ref "SB57") (pin "2") (pinfunction "2_2") (pintype "passive"))
      (node (ref "SB59") (pin "1") (pinfunction "1_1") (pintype "passive"))
    )
    (net (code "33") (name "/PB6") (class "Default")
      (node (ref "CN12") (pin "17") (pinfunction "17_17") (pintype "passive"))
    )
    (net (code "34") (name "/PB7") (class "Default")
      (node (ref "CN11") (pin "21") (pinfunction "21_21") (pintype "passive"))
    )
    (net (code "35") (name "/PB8") (class "Default")
      (node (ref "CN12") (pin "3") (pinfunction "3_3") (pintype "passive"))
      (node (ref "CN7") (pin "2") (pinfunction "2_2") (pintype "passive"))
      (node (ref "SB39") (pin "1") (pinfunction "1_1") (pintype "passive"))
    )
    (net (code "36") (name "/PB9") (class "Default")
      (node (ref "CN12") (pin "5") (pinfunction "5_5") (pintype "passive"))
      (node (ref "CN7") (pin "4") (pinfunction "4_4") (pintype "passive"))
      (node (ref "SB62") (pin "1") (pinfunction "1_1") (pintype "passive"))
    )
    (net (code "37") (name "/PB10") (class "Default")
      (node (ref "CN10") (pin "32") (pinfunction "32_32") (pintype "passive"))
      (node (ref "CN12") (pin "25") (pinfunction "25_25") (pintype "passive"))
    )
    (net (code "38") (name "/PB11") (class "Default")
      (node (ref "CN10") (pin "34") (pinfunction "34_34") (pintype "passive"))
      (node (ref "CN12") (pin "18") (pinfunction "18_18") (pintype "passive"))
    )
    (net (code "39") (name "/PB12") (class "Default")
      (node (ref "CN12") (pin "16") (pinfunction "16_16") (pintype "passive"))
      (node (ref "CN7") (pin "7") (pinfunction "7_7") (pintype "passive"))
    )
    (net (code "40") (name "/PB13") (class "Default")
      (node (ref "SB43") (pin "1") (pinfunction "1_1") (pintype "passive"))
      (node (ref "SB8") (pin "1") (pinfunction "1_1") (pintype "passive"))
    )
    (net (code "41") (name "/PB14") (class "Default")
      (node (ref "CN9") (pin "29") (pinfunction "29_29") (pintype "passive"))
      (node (ref "R75") (pin "1") (pinfunction "1_1") (pintype "passive"))
      (node (ref "SB37") (pin "1") (pinfunction "1_1") (pintype "passive"))
    )
    (net (code "42") (name "/PB15") (class "Default")
      (node (ref "CN12") (pin "26") (pinfunction "26_26") (pintype "passive"))
      (node (ref "CN7") (pin "3") (pinfunction "3_3") (pintype "passive"))
    )
    (net (code "44") (name "/PC0") (class "Default")
      (node (ref "CN11") (pin "38") (pinfunction "38_38") (pintype "passive"))
      (node (ref "CN9") (pin "3") (pinfunction "3_3") (pintype "passive"))
    )
    (net (code "45") (name "/PC1") (class "Default")
      (node (ref "CN11") (pin "36") (pinfunction "36_36") (pintype "passive"))
      (node (ref "SB70") (pin "1") (pinfunction "1_1") (pintype "passive"))
    )
    (net (code "46") (name "/PC2") (class "Default")
      (node (ref "CN11") (pin "35") (pinfunction "35_35") (pintype "passive"))
      (node (ref "SB69") (pin "1") (pinfunction "1_1") (pintype "passive"))
    )
    (net (code "47") (name "/PC3") (class "Default")
      (node (ref "CN11") (pin "37") (pinfunction "37_37") (pintype "passive"))
      (node (ref "CN9") (pin "5") (pinfunction "5_5") (pintype "passive"))
    )
    (net (code "48") (name "/PC4") (class "Default")
      (node (ref "CN12") (pin "34") (pinfunction "34_34") (pintype "passive"))
    )
    (net (code "49") (name "/PC5") (class "Default")
      (node (ref "CN12") (pin "6") (pinfunction "6_6") (pintype "passive"))
      (node (ref "SB58") (pin "1") (pinfunction "1_1") (pintype "passive"))
    )
    (net (code "50") (name "/PC6") (class "Default")
      (node (ref "CN12") (pin "4") (pinfunction "4_4") (pintype "passive"))
      (node (ref "CN7") (pin "1") (pinfunction "1_1") (pintype "passive"))
    )
    (net (code "51") (name "/PC7") (class "Default")
      (node (ref "CN12") (pin "19") (pinfunction "19_19") (pintype "passive"))
      (node (ref "CN7") (pin "11") (pinfunction "11_11") (pintype "passive"))
    )
    (net (code "52") (name "/PC8") (class "Default")
      (node (ref "CN8") (pin "2") (pinfunction "2_2") (pintype "passive"))
      (node (ref "SB20") (pin "2") (pinfunction "2_2") (pintype "passive"))
    )
    (net (code "53") (name "/PC9") (class "Default")
      (node (ref "CN8") (pin "4") (pinfunction "4_4") (pintype "passive"))
      (node (ref "SB9") (pin "1") (pinfunction "1_1") (pintype "passive"))
    )
    (net (code "54") (name "/PC10") (class "Default")
      (node (ref "CN11") (pin "1") (pinfunction "1_1") (pintype "passive"))
      (node (ref "CN8") (pin "6") (pinfunction "6_6") (pintype "passive"))
    )
    (net (code "55") (name "/PC11") (class "Default")
      (node (ref "CN11") (pin "2") (pinfunction "2_2") (pintype "passive"))
      (node (ref "CN8") (pin "8") (pinfunction "8_8") (pintype "passive"))
    )
    (net (code "56") (name "/PC12") (class "Default")
      (node (ref "CN11") (pin "3") (pinfunction "3_3") (pintype "passive"))
      (node (ref "CN8") (pin "10") (pinfunction "10_10") (pintype "passive"))
    )
    (net (code "57") (name "/PC13") (class "Default")
      (node (ref "CN11") (pin "23") (pinfunction "23_23") (pintype "passive"))
    )
    (net (code "58") (name "/PC14") (class "Default")
      (node (ref "CN11") (pin "25") (pinfunction "25_25") (pintype "passive"))
    )
    (net (code "59") (name "/PC15") (class "Default")
      (node (ref "CN11") (pin "27") (pinfunction "27_27") (pintype "passive"))
    )
    (net (code "61") (name "/PD0") (class "Default")
      (node (ref "CN11") (pin "57") (pinfunction "57_57") (pintype "passive"))
      (node (ref "CN9") (pin "25") (pinfunction "25_25") (pintype "passive"))
    )
    (net (code "62") (name "/PD1") (class "Default")
      (node (ref "CN11") (pin "55") (pinfunction "55_55") (pintype "passive"))
      (node (ref "CN9") (pin "27") (pinfunction "27_27") (pintype "passive"))
    )
    (net (code "63") (name "/PD2") (class "Default")
      (node (ref "CN11") (pin "4") (pinfunction "4_4") (pintype "passive"))
      (node (ref "CN8") (pin "12") (pinfunction "12_12") (pintype "passive"))
    )
    (net (code "64") (name "/PD3") (class "Default")
      (node (ref "CN11") (pin "40") (pinfunction "40_40") (pintype "passive"))
      (node (ref "CN9") (pin "10") (pinfunction "10_10") (pintype "passive"))
    )
    (net (code "65") (name "/PD4") (class "Default")
      (node (ref "CN11") (pin "39") (pinfunction "39_39") (pintype "passive"))
      (node (ref "CN9") (pin "8") (pinfunction "8_8") (pintype "passive"))
    )
    (net (code "66") (name "/PD5") (class "Default")
      (node (ref "CN11") (pin "41") (pinfunction "41_41") (pintype "passive"))
      (node (ref "CN9") (pin "6") (pinfunction "6_6") (pintype "passive"))
    )
    (net (code "67") (name "/PD6") (class "Default")
      (node (ref "CN11") (pin "43") (pinfunction "43_43") (pintype "passive"))
      (node (ref "CN9") (pin "4") (pinfunction "4_4") (pintype "passive"))
    )
    (net (code "68") (name "/PD7") (class "Default")
      (node (ref "CN11") (pin "45") (pinfunction "45_45") (pintype "passive"))
      (node (ref "CN9") (pin "2") (pinfunction "2_2") (pintype "passive"))
    )
    (net (code "69") (name "/PD8") (class "Default")
      (node (ref "CN12") (pin "10") (pinfunction "10_10") (pintype "passive"))
    )
    (net (code "70") (name "/PD9") (class "Default")
      (node (ref "CN11") (pin "69") (pinfunction "69_69") (pintype "passive"))
    )
    (net (code "71") (name "/PD10") (class "Default")
      (node (ref "CN12") (pin "65") (pinfunction "65_65") (pintype "passive"))
      (node (ref "SB99") (pin "2") (pinfunction "2_2") (pintype "passive"))
    )
    (net (code "72") (name "/PD11") (class "Default")
      (node (ref "CN10") (pin "23") (pinfunction "23_23") (pintype "passive"))
      (node (ref "CN12") (pin "45") (pinfunction "45_45") (pintype "passive"))
    )
    (net (code "73") (name "/PD12") (class "Default")
      (node (ref "CN10") (pin "21") (pinfunction "21_21") (pintype "passive"))
      (node (ref "CN12") (pin "43") (pinfunction "43_43") (pintype "passive"))
    )
    (net (code "74") (name "/PD13") (class "Default")
      (node (ref "CN10") (pin "19") (pinfunction "19_19") (pintype "passive"))
      (node (ref "CN12") (pin "41") (pinfunction "41_41") (pintype "passive"))
    )
    (net (code "75") (name "/PD14") (class "Default")
      (node (ref "CN12") (pin "46") (pinfunction "46_46") (pintype "passive"))
      (node (ref "CN7") (pin "16") (pinfunction "16_16") (pintype "passive"))
    )
    (net (code "76") (name "/PD15") (class "Default")
      (node (ref "CN12") (pin "48") (pinfunction "48_48") (pintype "passive"))
      (node (ref "CN7") (pin "18") (pinfunction "18_18") (pintype "passive"))
    )
    (net (code "78") (name "/PE0") (class "Default")
      (node (ref "CN10") (pin "33") (pinfunction "33_33") (pintype "passive"))
      (node (ref "CN12") (pin "64") (pinfunction "64_64") (pintype "passive"))
    )
    (net (code "79") (name "/PE1") (class "Default")
      (node (ref "CN11") (pin "61") (pinfunction "61_61") (pintype "passive"))
      (node (ref "R74") (pin "1") (pinfunction "1_1") (pintype "passive"))
    )
    (net (code "80") (name "/PE2") (class "Default")
      (node (ref "CN11") (pin "46") (pinfunction "46_46") (pintype "passive"))
      (node (ref "SB87") (pin "1") (pinfunction "1_1") (pintype "passive"))
      (node (ref "SB88") (pin "2") (pinfunction "2_2") (pintype "passive"))
    )
    (net (code "81") (name "/PE3") (class "Default")
      (node (ref "CN11") (pin "47") (pinfunction "47_47") (pintype "passive"))
      (node (ref "CN9") (pin "22") (pinfunction "22_22") (pintype "passive"))
    )
    (net (code "82") (name "/PE4") (class "Default")
      (node (ref "CN11") (pin "48") (pinfunction "48_48") (pintype "passive"))
      (node (ref "CN9") (pin "16") (pinfunction "16_16") (pintype "passive"))
    )
    (net (code "83") (name "/PE5") (class "Default")
      (node (ref "CN11") (pin "50") (pinfunction "50_50") (pintype "passive"))
      (node (ref "CN9") (pin "18") (pinfunction "18_18") (pintype "passive"))
    )
    (net (code "84") (name "/PE6") (class "Default")
      (node (ref "CN11") (pin "62") (pinfunction "62_62") (pintype "passive"))
      (node (ref "SB10") (pin "1") (pinfunction "1_1") (pintype "passive"))
      (node (ref "SB85") (pin "2") (pinfunction "2_2") (pintype "passive"))
      (node (ref "SB86") (pin "2") (pinfunction "2_2") (pintype "passive"))
    )
    (net (code "85") (name "/PE7") (class "Default")
      (node (ref "CN10") (pin "20") (pinfunction "20_20") (pintype "passive"))
      (node (ref "CN12") (pin "44") (pinfunction "44_44") (pintype "passive"))
    )
    (net (code "86") (name "/PE8") (class "Default")
      (node (ref "CN10") (pin "18") (pinfunction "18_18") (pintype "passive"))
      (node (ref "CN12") (pin "40") (pinfunction "40_40") (pintype "passive"))
      (node (ref "SB47") (pin "1") (pinfunction "1_1") (pintype "passive"))
    )
    (net (code "87") (name "/PE9") (class "Default")
      (node (ref "CN12") (pin "52") (pinfunction "52_52") (pintype "passive"))
      (node (ref "CN9") (pin "15") (pinfunction "15_15") (pintype "passive"))
    )
    (net (code "88") (name "/PE10") (class "Default")
      (node (ref "CN10") (pin "24") (pinfunction "24_24") (pintype "passive"))
      (node (ref "CN12") (pin "47") (pinfunction "47_47") (pintype "passive"))
    )
    (net (code "89") (name "/PE11") (class "Default")
      (node (ref "CN10") (pin "6") (pinfunction "6_6") (pintype "passive"))
      (node (ref "CN12") (pin "56") (pinfunction "56_56") (pintype "passive"))
    )
    (net (code "90") (name "/PE12") (class "Default")
      (node (ref "CN10") (pin "26") (pinfunction "26_26") (pintype "passive"))
      (node (ref "CN12") (pin "49") (pinfunction "49_49") (pintype "passive"))
    )
    (net (code "91") (name "/PE13") (class "Default")
      (node (ref "CN10") (pin "10") (pinfunction "10_10") (pintype "passive"))
      (node (ref "CN12") (pin "55") (pinfunction "55_55") (pintype "passive"))
    )
    (net (code "92") (name "/PE14") (class "Default")
      (node (ref "CN10") (pin "8") (pinfunction "8_8") (pintype "passive"))
      (node (ref "CN12") (pin "51") (pinfunction "51_51") (pintype "passive"))
    )
    (net (code "93") (name "/PE15") (class "Default")
      (node (ref "CN10") (pin "30") (pinfunction "30_30") (pintype "passive"))
      (node (ref "CN12") (pin "53") (pinfunction "53_53") (pintype "passive"))
      (node (ref "SB38") (pin "1") (pinfunction "1_1") (pintype "passive"))
    )
    (net (code "95") (name "/PF6") (class "Default")
      (node (ref "CN11") (pin "9") (pinfunction "9_9") (pintype "passive"))
      (node (ref "SB73") (pin "1") (pinfunction "1_1") (pintype "passive"))
    )
    (net (code "96") (name "/PF7") (class "Default")
      (node (ref "CN11") (pin "11") (pinfunction "11_11") (pintype "passive"))
      (node (ref "CN9") (pin "26") (pinfunction "26_26") (pintype "passive"))
    )
    (net (code "97") (name "/PF8") (class "Default")
      (node (ref "CN11") (pin "54") (pinfunction "54_54") (pintype "passive"))
      (node (ref "CN9") (pin "24") (pinfunction "24_24") (pintype "passive"))
    )
    (net (code "98") (name "/PF9") (class "Default")
      (node (ref "CN11") (pin "56") (pinfunction "56_56") (pintype "passive"))
      (node (ref "CN9") (pin "28") (pinfunction "28_28") (pintype "passive"))
    )
    (net (code "99") (name "/PF10") (class "Default")
      (node (ref "CN12") (pin "42") (pinfunction "42_42") (pintype "passive"))
      (node (ref "SB93") (pin "1") (pinfunction "1_1") (pintype "passive"))
    )
    (net (code "100") (name "/PF11") (class "Default")
      (node (ref "CN12") (pin "62") (pinfunction "62_62") (pintype "passive"))
      (node (ref "SB40") (pin "1") (pinfunction "1_1") (pintype "passive"))
    )
    (net (code "101") (name "/PF14") (class "Default")
      (node (ref "CN12") (pin "50") (pinfunction "50_50") (pintype "passive"))
      (node (ref "CN9") (pin "19") (pinfunction "19_19") (pintype "passive"))
    )
    (net (code "102") (name "/PF15") (class "Default")
      (node (ref "CN12") (pin "60") (pinfunction "60_60") (pintype "passive"))
      (node (ref "CN9") (pin "21") (pinfunction "21_21") (pintype "passive"))
    )
    (net (code "105") (name "/PG6") (class "Default")
      (node (ref "CN10") (pin "13") (pinfunction "13_13") (pintype "passive"))
      (node (ref "CN12") (pin "70") (pinfunction "70_70") (pintype "passive"))
    )
    (net (code "106") (name "/PG7") (class "Default")
      (node (ref "CN12") (pin "67") (pinfunction "67_67") (pintype "passive"))
    )
    (net (code "107") (name "/PG8") (class "Default")
      (node (ref "CN12") (pin "66") (pinfunction "66_66") (pintype "passive"))
      (node (ref "SB31") (pin "2") (pinfunction "2_2") (pintype "passive"))
      (node (ref "SB34") (pin "2") (pinfunction "2_2") (pintype "passive"))
    )
    (net (code "108") (name "/PG9") (class "Default")
      (node (ref "CN11") (pin "63") (pinfunction "63_63") (pintype "passive"))
      (node (ref "SB35") (pin "2") (pinfunction "2_2") (pintype "passive"))
      (node (ref "SB41") (pin "2") (pinfunction "2_2") (pintype "passive"))
    )
    (net (code "109") (name "/PG10") (class "Default")
      (node (ref "CN11") (pin "66") (pinfunction "66_66") (pintype "passive"))
      (node (ref "SB30") (pin "2") (pinfunction "2_2") (pintype "passive"))
      (node (ref "SB33") (pin "2") (pinfunction "2_2") (pintype "passive"))
    )
    (net (code "110") (name "/PG11") (class "Default")
      (node (ref "CN11") (pin "70") (pinfunction "70_70") (pintype "passive"))
    )
    (net (code "111") (name "/PG12") (class "Default")
      (node (ref "CN11") (pin "65") (pinfunction "65_65") (pintype "passive"))
      (node (ref "SB42") (pin "2") (pinfunction "2_2") (pintype "passive"))
      (node (ref "SB45") (pin "2") (pinfunction "2_2") (pintype "passive"))
    )
    (net (code "112") (name "/PG13") (class "Default")
      (node (ref "CN11") (pin "68") (pinfunction "68_68") (pintype "passive"))
    )
    (net (code "113") (name "/PG14") (class "Default")
      (node (ref "CN10") (pin "12") (pinfunction "12_12") (pintype "passive"))
      (node (ref "CN12") (pin "61") (pinfunction "61_61") (pintype "passive"))
    )
    (net (code "115") (name "/PH0") (class "Default")
      (node (ref "CN11") (pin "29") (pinfunction "29_29") (pintype "passive"))
    )
    (net (code "116") (name "/PH1") (class "Default")
      (node (ref "CN11") (pin "31") (pinfunction "31_31") (pintype "passive"))
    )
    (net (code "118") (name "/SMPS_EN") (class "Default")
      (node (ref "CN6") (pin "4") (pinfunction "4_4") (pintype "passive"))
      (node (ref "SB35") (pin "1") (pinfunction "1_1") (pintype "passive"))
    )
    (net (code "119") (name "/SMPS_PG") (class "Default")
      (node (ref "CN6") (pin "8") (pinfunction "8_8") (pintype "passive"))
      (node (ref "SB42") (pin "1") (pinfunction "1_1") (pintype "passive"))
    )
    (net (code "120") (name "/SMPS_SW") (class "Default")
      (node (ref "CN6") (pin "6") (pinfunction "6_6") (pintype "passive"))
      (node (ref "SB33") (pin "1") (pinfunction "1_1") (pintype "passive"))
    )
    (net (code "121") (name "/SMPS_V1") (class "Default")
      (node (ref "CN6") (pin "2") (pinfunction "2_2") (pintype "passive"))
      (node (ref "SB34") (pin "1") (pinfunction "1_1") (pintype "passive"))
    )
    (net (code "122") (name "1V2_MCU") (class "Default")
      (node (ref "SB95") (pin "2") (pinfunction "2_2") (pintype "passive"))
    )
    (net (code "123") (name "1V2_VOUTCORE") (class "Default")
      (node (ref "CN6") (pin "5") (pinfunction "5_5") (pintype "passive"))
      (node (ref "SB95") (pin "1") (pinfunction "1_1") (pintype "passive"))
    )
    (net (code "124") (name "3V3") (class "Default")
      (node (ref "CN11") (pin "16") (pinfunction "16_16") (pintype "passive"))
      (node (ref "CN6") (pin "1") (pinfunction "1_1") (pintype "passive"))
      (node (ref "CN8") (pin "7") (pinfunction "7_7") (pintype "passive"))
      (node (ref "R26") (pin "2") (pinfunction "2_2") (pintype "passive"))
      (node (ref "R27") (pin "2") (pinfunction "2_2") (pintype "passive"))
      (node (ref "R28") (pin "2") (pinfunction "2_2") (pintype "passive"))
      (node (ref "SB24") (pin "1") (pinfunction "1_1") (pintype "passive"))
    )
    (net (code "125") (name "5V") (class "Default")
      (node (ref "CN11") (pin "18") (pinfunction "18_18") (pintype "passive"))
      (node (ref "CN8") (pin "9") (pinfunction "9_9") (pintype "passive"))
    )
    (net (code "126") (name "5V_EXT") (class "Default")
      (node (ref "CN11") (pin "6") (pinfunction "6_6") (pintype "passive"))
    )
    (net (code "127") (name "5V_USB_STLK") (class "Default")
      (node (ref "CN12") (pin "8") (pinfunction "8_8") (pintype "passive"))
    )
    (net (code "128") (name "AGND") (class "Default")
      (node (ref "C70") (pin "1") (pinfunction "1_1") (pintype "passive"))
      (node (ref "CN10") (pin "3") (pinfunction "3_3") (pintype "passive"))
      (node (ref "CN12") (pin "32") (pinfunction "32_32") (pintype "passive"))
    )
    (net (code "129") (name "GND") (class "Default")
      (node (ref "CN10") (pin "17") (pinfunction "17_17") (pintype "passive"))
      (node (ref "CN10") (pin "22") (pinfunction "22_22") (pintype "passive"))
      (node (ref "CN10") (pin "27") (pinfunction "27_27") (pintype "passive"))
      (node (ref "CN10") (pin "5") (pinfunction "5_5") (pintype "passive"))
      (node (ref "CN11") (pin "19") (pinfunction "19_19") (pintype "passive"))
      (node (ref "CN11") (pin "20") (pinfunction "20_20") (pintype "passive"))
      (node (ref "CN11") (pin "22") (pinfunction "22_22") (pintype "passive"))
      (node (ref "CN11") (pin "49") (pinfunction "49_49") (pintype "passive"))
      (node (ref "CN11") (pin "60") (pinfunction "60_60") (pintype "passive"))
      (node (ref "CN11") (pin "8") (pinfunction "8_8") (pintype "passive"))
      (node (ref "CN12") (pin "20") (pinfunction "20_20") (pintype "passive"))
      (node (ref "CN12") (pin "39") (pinfunction "39_39") (pintype "passive"))
      (node (ref "CN12") (pin "54") (pinfunction "54_54") (pintype "passive"))
      (node (ref "CN12") (pin "63") (pinfunction "63_63") (pintype "passive"))
      (node (ref "CN12") (pin "9") (pinfunction "9_9") (pintype "passive"))
      (node (ref "CN15") (pin "1") (pinfunction "COMMON_1") (pintype "passive"))
      (node (ref "CN15") (pin "2") (pinfunction "NO_2") (pintype "passive"))
      (node (ref "CN16") (pin "1") (pinfunction "COMMON_1") (pintype "passive"))
      (node (ref "CN16") (pin "2") (pinfunction "NO_2") (pintype "passive"))
      (node (ref "CN6") (pin "7") (pinfunction "7_7") (pintype "passive"))
      (node (ref "CN7") (pin "8") (pinfunction "8_8") (pintype "passive"))
      (node (ref "CN8") (pin "11") (pinfunction "11_11") (pintype "passive"))
      (node (ref "CN8") (pin "13") (pinfunction "13_13") (pintype "passive"))
      (node (ref "CN9") (pin "12") (pinfunction "12_12") (pintype "passive"))
      (node (ref "CN9") (pin "23") (pinfunction "23_23") (pintype "passive"))
      (node (ref "Q1") (pin "2") (pinfunction "E_2") (pintype "passive"))
      (node (ref "Q2") (pin "2") (pinfunction "E_2") (pintype "passive"))
      (node (ref "Q3") (pin "2") (pinfunction "E_2") (pintype "passive"))
      (node (ref "R71") (pin "1") (pinfunction "1_1") (pintype "passive"))
      (node (ref "R72") (pin "1") (pinfunction "1_1") (pintype "passive"))
      (node (ref "R73") (pin "1") (pinfunction "1_1") (pintype "passive"))
    )
    (net (code "130") (name "IOREF") (class "Default")
      (node (ref "CN11") (pin "12") (pinfunction "12_12") (pintype "passive"))
      (node (ref "CN8") (pin "3") (pinfunction "3_3") (pintype "passive"))
      (node (ref "SB14") (pin "2") (pinfunction "2_2") (pintype "passive"))
      (node (ref "SB24") (pin "2") (pinfunction "2_2") (pintype "passive"))
    )
    (net (code "131") (name "Net-(CN7-Pad5)") (class "Default")
      (node (ref "CN7") (pin "5") (pinfunction "5_5") (pintype "passive"))
      (node (ref "SB8") (pin "2") (pinfunction "2_2") (pintype "passive"))
    )
    (net (code "132") (name "Net-(CN7-Pad13)") (class "Default")
      (node (ref "CN7") (pin "13") (pinfunction "13_13") (pintype "passive"))
      (node (ref "SB53") (pin "2") (pinfunction "2_2") (pintype "passive"))
    )
    (net (code "133") (name "Net-(CN7-Pad14)") (class "Default")
      (node (ref "CN7") (pin "14") (pinfunction "14_14") (pintype "passive"))
      (node (ref "SB56") (pin "1") (pinfunction "1_1") (pintype "passive"))
      (node (ref "SB57") (pin "1") (pinfunction "1_1") (pintype "passive"))
    )
    (net (code "134") (name "Net-(CN7-Pad15)") (class "Default")
      (node (ref "CN7") (pin "15") (pinfunction "15_15") (pintype "passive"))
      (node (ref "SB49") (pin "2") (pinfunction "2_2") (pintype "passive"))
    )
    (net (code "135") (name "Net-(CN7-Pad20)") (class "Default")
      (node (ref "CN7") (pin "20") (pinfunction "20_20") (pintype "passive"))
      (node (ref "SB41") (pin "1") (pinfunction "1_1") (pintype "passive"))
    )
    (net (code "136") (name "Net-(CN8-Pad14)") (class "Default")
      (node (ref "CN8") (pin "14") (pinfunction "14_14") (pintype "passive"))
      (node (ref "SB30") (pin "1") (pinfunction "1_1") (pintype "passive"))
    )
    (net (code "137") (name "Net-(CN8-Pad16)") (class "Default")
      (node (ref "CN8") (pin "16") (pinfunction "16_16") (pintype "passive"))
      (node (ref "SB31") (pin "1") (pinfunction "1_1") (pintype "passive"))
    )
    (net (code "138") (name "Net-(CN9-Pad9)") (class "Default")
      (node (ref "CN9") (pin "9") (pinfunction "9_9") (pintype "passive"))
      (node (ref "SB62") (pin "2") (pinfunction "2_2") (pintype "passive"))
      (node (ref "SB69") (pin "2") (pinfunction "2_2") (pintype "passive"))
    )
    (net (code "139") (name "Net-(CN9-Pad11)") (class "Default")
      (node (ref "CN9") (pin "11") (pinfunction "11_11") (pintype "passive"))
      (node (ref "SB39") (pin "2") (pinfunction "2_2") (pintype "passive"))
      (node (ref "SB40") (pin "2") (pinfunction "2_2") (pintype "passive"))
    )
    (net (code "140") (name "Net-(CN9-Pad13)") (class "Default")
      (node (ref "CN9") (pin "13") (pinfunction "13_13") (pintype "passive"))
      (node (ref "SB44") (pin "2") (pinfunction "2_2") (pintype "passive"))
    )
    (net (code "141") (name "Net-(CN9-Pad14)") (class "Default")
      (node (ref "CN9") (pin "14") (pinfunction "14_14") (pintype "passive"))
      (node (ref "SB88") (pin "1") (pinfunction "1_1") (pintype "passive"))
    )
    (net (code "142") (name "Net-(CN9-Pad17)") (class "Default")
      (node (ref "CN9") (pin "17") (pinfunction "17_17") (pintype "passive"))
      (node (ref "SB55") (pin "2") (pinfunction "2_2") (pintype "passive"))
    )
    (net (code "143") (name "Net-(CN9-Pad20)") (class "Default")
      (node (ref "CN9") (pin "20") (pinfunction "20_20") (pintype "passive"))
      (node (ref "SB86") (pin "1") (pinfunction "1_1") (pintype "passive"))
    )
    (net (code "144") (name "Net-(CN9-Pad30)") (class "Default")
      (node (ref "CN9") (pin "30") (pinfunction "30_30") (pintype "passive"))
      (node (ref "SB99") (pin "1") (pinfunction "1_1") (pintype "passive"))
    )
    (net (code "145") (name "Net-(CN10-Pad2)") (class "Default")
      (node (ref "CN10") (pin "2") (pinfunction "2_2") (pintype "passive"))
      (node (ref "SB45") (pin "1") (pinfunction "1_1") (pintype "passive"))
    )
    (net (code "146") (name "Net-(CN10-Pad4)") (class "Default")
      (node (ref "CN10") (pin "4") (pinfunction "4_4") (pintype "passive"))
      (node (ref "SB28") (pin "1") (pinfunction "1_1") (pintype "passive"))
    )
    (net (code "147") (name "Net-(CN10-Pad7)") (class "Default")
      (node (ref "CN10") (pin "7") (pinfunction "7_7") (pintype "passive"))
      (node (ref "SB70") (pin "2") (pinfunction "2_2") (pintype "passive"))
      (node (ref "SB73") (pin "2") (pinfunction "2_2") (pintype "passive"))
    )
    (net (code "148") (name "Net-(CN10-Pad9)") (class "Default")
      (node (ref "CN10") (pin "9") (pinfunction "9_9") (pintype "passive"))
      (node (ref "SB58") (pin "2") (pinfunction "2_2") (pintype "passive"))
      (node (ref "SB93") (pin "2") (pinfunction "2_2") (pintype "passive"))
    )
    (net (code "149") (name "Net-(CN10-Pad11)") (class "Default")
      (node (ref "CN10") (pin "11") (pinfunction "11_11") (pintype "passive"))
      (node (ref "SB78") (pin "2") (pinfunction "2_2") (pintype "passive"))
    )
    (net (code "150") (name "Net-(CN10-Pad15)") (class "Default")
      (node (ref "CN10") (pin "15") (pinfunction "15_15") (pintype "passive"))
      (node (ref "SB51") (pin "2") (pinfunction "2_2") (pintype "passive"))
    )
    (net (code "151") (name "Net-(CN10-Pad25)") (class "Default")
      (node (ref "CN10") (pin "25") (pinfunction "25_25") (pintype "passive"))
      (node (ref "SB87") (pin "2") (pinfunction "2_2") (pintype "passive"))
    )
    (net (code "152") (name "Net-(CN10-Pad28)") (class "Default")
      (node (ref "CN10") (pin "28") (pinfunction "28_28") (pintype "passive"))
      (node (ref "SB85") (pin "1") (pinfunction "1_1") (pintype "passive"))
    )
    (net (code "153") (name "Net-(CN10-Pad29)") (class "Default")
      (node (ref "CN10") (pin "29") (pinfunction "29_29") (pintype "passive"))
      (node (ref "SB89") (pin "2") (pinfunction "2_2") (pintype "passive"))
    )
    (net (code "154") (name "Net-(CN12-Pad1)") (class "Default")
      (node (ref "CN12") (pin "1") (pinfunction "1_1") (pintype "passive"))
      (node (ref "SB9") (pin "2") (pinfunction "2_2") (pintype "passive"))
    )
    (net (code "155") (name "Net-(CN12-Pad2)") (class "Default")
      (node (ref "CN12") (pin "2") (pinfunction "2_2") (pintype "passive"))
      (node (ref "SB20") (pin "1") (pinfunction "1_1") (pintype "passive"))
    )
    (net (code "156") (name "Net-(CN12-Pad7)") (class "Default")
      (node (ref "CN12") (pin "7") (pinfunction "7_7") (pintype "passive"))
      (node (ref "CN7") (pin "6") (pinfunction "6_6") (pintype "passive"))
      (node (ref "SB60") (pin "1") (pinfunction "1_1") (pintype "passive"))
    )
    (net (code "157") (name "Net-(LD1-Pad1)") (class "Default")
      (node (ref "LD1") (pin "1") (pintype "passive"))
      (node (ref "R28") (pin "1") (pinfunction "1_1") (pintype "passive"))
    )
    (net (code "158") (name "Net-(LD2-Pad1)") (class "Default")
      (node (ref "LD2") (pin "1") (pintype "passive"))
      (node (ref "R27") (pin "1") (pinfunction "1_1") (pintype "passive"))
    )
    (net (code "159") (name "Net-(LD3-Pad1)") (class "Default")
      (node (ref "LD3") (pin "1") (pintype "passive"))
      (node (ref "R26") (pin "1") (pinfunction "1_1") (pintype "passive"))
    )
    (net (code "160") (name "Net-(Q1-B)") (class "Default")
      (node (ref "Q1") (pin "1") (pinfunction "B_1") (pintype "passive"))
      (node (ref "R71") (pin "2") (pinfunction "2_2") (pintype "passive"))
      (node (ref "R76") (pin "2") (pinfunction "2_2") (pintype "passive"))
    )
    (net (code "161") (name "Net-(Q1-C)") (class "Default")
      (node (ref "LD1") (pin "2") (pintype "passive"))
      (node (ref "Q1") (pin "3") (pinfunction "C_3") (pintype "passive"))
    )
    (net (code "162") (name "Net-(Q2-B)") (class "Default")
      (node (ref "Q2") (pin "1") (pinfunction "B_1") (pintype "passive"))
      (node (ref "R72") (pin "2") (pinfunction "2_2") (pintype "passive"))
      (node (ref "R74") (pin "2") (pinfunction "2_2") (pintype "passive"))
    )
    (net (code "163") (name "Net-(Q2-C)") (class "Default")
      (node (ref "LD2") (pin "2") (pintype "passive"))
      (node (ref "Q2") (pin "3") (pinfunction "C_3") (pintype "passive"))
    )
    (net (code "164") (name "Net-(Q3-B)") (class "Default")
      (node (ref "Q3") (pin "1") (pinfunction "B_1") (pintype "passive"))
      (node (ref "R73") (pin "2") (pinfunction "2_2") (pintype "passive"))
      (node (ref "R75") (pin "2") (pinfunction "2_2") (pintype "passive"))
    )
    (net (code "165") (name "Net-(Q3-C)") (class "Default")
      (node (ref "LD3") (pin "2") (pintype "passive"))
      (node (ref "Q3") (pin "3") (pinfunction "C_3") (pintype "passive"))
    )
    (net (code "166") (name "Net-(R76-Pad1)") (class "Default")
      (node (ref "R76") (pin "1") (pinfunction "1_1") (pintype "passive"))
      (node (ref "SB54") (pin "2") (pinfunction "2_2") (pintype "passive"))
      (node (ref "SB65") (pin "2") (pinfunction "2_2") (pintype "passive"))
    )
    (net (code "167") (name "VBAT") (class "Default")
      (node (ref "CN11") (pin "33") (pinfunction "33_33") (pintype "passive"))
    )
    (net (code "168") (name "VDD") (class "Default")
      (node (ref "CN11") (pin "5") (pinfunction "5_5") (pintype "passive"))
      (node (ref "SB14") (pin "1") (pinfunction "1_1") (pintype "passive"))
    )
    (net (code "169") (name "VDDA") (class "Default")
      (node (ref "CN10") (pin "1") (pinfunction "1_1") (pintype "passive"))
    )
    (net (code "170") (name "VIN") (class "Default")
      (node (ref "CN11") (pin "24") (pinfunction "24_24") (pintype "passive"))
      (node (ref "CN8") (pin "15") (pinfunction "15_15") (pintype "passive"))
    )
    (net (code "171") (name "VOUTVDD") (class "Default")
      (node (ref "CN6") (pin "3") (pinfunction "3_3") (pintype "passive"))
    )
    (net (code "172") (name "VREFP") (class "Default")
      (node (ref "C70") (pin "2") (pinfunction "2_2") (pintype "passive"))
      (node (ref "SB60") (pin "2") (pinfunction "2_2") (pintype "passive"))
    )
    (net (code "173") (name "unconnected-(CN8-Pad1)") (class "Default")
      (node (ref "CN8") (pin "1") (pinfunction "1_1") (pintype "passive+no_connect"))
    )
    (net (code "174") (name "unconnected-(CN11-Pad10)") (class "Default")
      (node (ref "CN11") (pin "10") (pinfunction "10_10") (pintype "passive+no_connect"))
    )
    (net (code "175") (name "unconnected-(CN11-Pad26)") (class "Default")
      (node (ref "CN11") (pin "26") (pinfunction "26_26") (pintype "passive+no_connect"))
    )
    (net (code "176") (name "unconnected-(CN11-Pad42)") (class "Default")
      (node (ref "CN11") (pin "42") (pinfunction "42_42") (pintype "passive+no_connect"))
    )
    (net (code "177") (name "unconnected-(CN11-Pad44)") (class "Default")
      (node (ref "CN11") (pin "44") (pinfunction "44_44") (pintype "passive+no_connect"))
    )
    (net (code "178") (name "unconnected-(CN11-Pad51)") (class "Default")
      (node (ref "CN11") (pin "51") (pinfunction "51_51") (pintype "passive+no_connect"))
    )
    (net (code "179") (name "unconnected-(CN11-Pad52)") (class "Default")
      (node (ref "CN11") (pin "52") (pinfunction "52_52") (pintype "passive+no_connect"))
    )
    (net (code "180") (name "unconnected-(CN11-Pad53)") (class "Default")
      (node (ref "CN11") (pin "53") (pinfunction "53_53") (pintype "passive+no_connect"))
    )
    (net (code "181") (name "unconnected-(CN11-Pad58)") (class "Default")
      (node (ref "CN11") (pin "58") (pinfunction "58_58") (pintype "passive+no_connect"))
    )
    (net (code "182") (name "unconnected-(CN11-Pad59)") (class "Default")
      (node (ref "CN11") (pin "59") (pinfunction "59_59") (pintype "passive+no_connect"))
    )
    (net (code "183") (name "unconnected-(CN11-Pad64)") (class "Default")
      (node (ref "CN11") (pin "64") (pinfunction "64_64") (pintype "passive+no_connect"))
    )
    (net (code "184") (name "unconnected-(CN11-Pad67)") (class "Default")
      (node (ref "CN11") (pin "67") (pinfunction "67_67") (pintype "passive+no_connect"))
    )
    (net (code "185") (name "unconnected-(CN12-Pad36)") (class "Default")
      (node (ref "CN12") (pin "36") (pinfunction "36_36") (pintype "passive+no_connect"))
    )
    (net (code "186") (name "unconnected-(CN12-Pad38)") (class "Default")
      (node (ref "CN12") (pin "38") (pinfunction "38_38") (pintype "passive+no_connect"))
    )
    (net (code "187") (name "unconnected-(CN12-Pad57)") (class "Default")
      (node (ref "CN12") (pin "57") (pinfunction "57_57") (pintype "passive+no_connect"))
    )
    (net (code "188") (name "unconnected-(CN12-Pad58)") (class "Default")
      (node (ref "CN12") (pin "58") (pinfunction "58_58") (pintype "passive+no_connect"))
    )
    (net (code "189") (name "unconnected-(CN12-Pad59)") (class "Default")
      (node (ref "CN12") (pin "59") (pinfunction "59_59") (pintype "passive+no_connect"))
    )
    (net (code "190") (name "unconnected-(CN12-Pad68)") (class "Default")
      (node (ref "CN12") (pin "68") (pinfunction "68_68") (pintype "passive+no_connect"))
    )
    (net (code "191") (name "unconnected-(CN12-Pad69)") (class "Default")
      (node (ref "CN12") (pin "69") (pinfunction "69_69") (pintype "passive+no_connect"))
    )
  )
)
